# ADG3300-BREAKOUT.net
KiCad netlist of a schematic drawn in Altium Designer
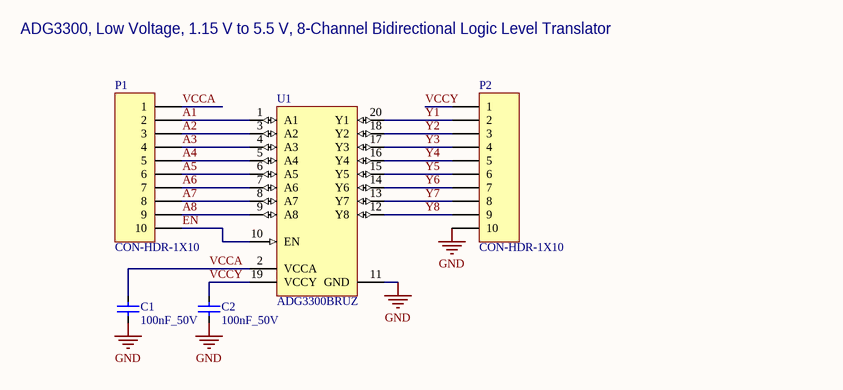
[diagram p0: ADG3300-BREAKOUT.SchDoc]

(export (version "E")
  (design (tool "Eeschema 10.0.6"))
  (components
    (comp (ref "C1")
      (value "100nF_50V")
      (footprint "CustomLib-Package:C0805")
      (description "50V 100nF X7R ±10% 0805 Multilayer Ceramic Capacitors MLCC - SMD/SMT ROHS")
      (fields (field (name "MANUFACTURER") "YAGEO") (field (name "Comment") "CC0805KRX7R9BB104"))
      (libsource (lib "CustomLib-Package") (part "CAPACITOR"))
    )
    (comp (ref "C2")
      (value "100nF_50V")
      (footprint "CustomLib-Package:C0805")
      (description "50V 100nF X7R ±10% 0805 Multilayer Ceramic Capacitors MLCC - SMD/SMT ROHS")
      (fields (field (name "MANUFACTURER") "YAGEO") (field (name "Comment") "CC0805KRX7R9BB104"))
      (libsource (lib "CustomLib-Package") (part "CAPACITOR"))
    )
    (comp (ref "P1")
      (value "CON-HDR-1X10")
      (footprint "CustomLib-Package:CON-HDR-1X10-2.54")
      (description "Pin Header, 10-Pin")
      (fields (field (name "PUBLISHER") "Altium Limited"))
      (libsource (lib "") (part "CON-HDR-1X10_1"))
    )
    (comp (ref "P2")
      (value "CON-HDR-1X10")
      (footprint "CustomLib-Package:CON-HDR-1X10-2.54")
      (description "Pin Header, 10-Pin")
      (fields (field (name "PUBLISHER") "Altium Limited"))
      (libsource (lib "CustomLib-Package") (part "CON-HDR-1X10"))
    )
    (comp (ref "U1")
      (value "ADG3300BRUZ")
      (footprint "CustomLib-Package:TSSOP-20")
      (fields (field (name "MANUFACTURER") "Analog Devices"))
      (libsource (lib "CustomLib-Package") (part "ADG3300"))
    )
  )
  (nets
    (net (code "1") (name "/A1") (class "Default")
      (node (ref "P1") (pin "2") (pinfunction "2_2") (pintype "passive"))
      (node (ref "U1") (pin "1") (pinfunction "A1_1") (pintype "bidirectional"))
    )
    (net (code "2") (name "/A2") (class "Default")
      (node (ref "P1") (pin "3") (pinfunction "3_3") (pintype "passive"))
      (node (ref "U1") (pin "3") (pinfunction "A2_3") (pintype "bidirectional"))
    )
    (net (code "3") (name "/A3") (class "Default")
      (node (ref "P1") (pin "4") (pinfunction "4_4") (pintype "passive"))
      (node (ref "U1") (pin "4") (pinfunction "A3_4") (pintype "bidirectional"))
    )
    (net (code "4") (name "/A4") (class "Default")
      (node (ref "P1") (pin "5") (pinfunction "5_5") (pintype "passive"))
      (node (ref "U1") (pin "5") (pinfunction "A4_5") (pintype "bidirectional"))
    )
    (net (code "5") (name "/A5") (class "Default")
      (node (ref "P1") (pin "6") (pinfunction "6_6") (pintype "passive"))
      (node (ref "U1") (pin "6") (pinfunction "A5_6") (pintype "bidirectional"))
    )
    (net (code "6") (name "/A6") (class "Default")
      (node (ref "P1") (pin "7") (pinfunction "7_7") (pintype "passive"))
      (node (ref "U1") (pin "7") (pinfunction "A6_7") (pintype "bidirectional"))
    )
    (net (code "7") (name "/A7") (class "Default")
      (node (ref "P1") (pin "8") (pinfunction "8_8") (pintype "passive"))
      (node (ref "U1") (pin "8") (pinfunction "A7_8") (pintype "bidirectional"))
    )
    (net (code "8") (name "/A8") (class "Default")
      (node (ref "P1") (pin "9") (pinfunction "9_9") (pintype "passive"))
      (node (ref "U1") (pin "9") (pinfunction "A8_9") (pintype "bidirectional"))
    )
    (net (code "9") (name "/EN") (class "Default")
      (node (ref "P1") (pin "10") (pinfunction "10_10") (pintype "passive"))
      (node (ref "U1") (pin "10") (pinfunction "EN_10") (pintype "input"))
    )
    (net (code "10") (name "/VCCA") (class "Default")
      (node (ref "C1") (pin "1") (pinfunction "1_1") (pintype "passive"))
      (node (ref "P1") (pin "1") (pinfunction "1_1") (pintype "passive"))
      (node (ref "U1") (pin "2") (pinfunction "VCCA_2") (pintype "power_in"))
    )
    (net (code "11") (name "/VCCY") (class "Default")
      (node (ref "C2") (pin "1") (pinfunction "1_1") (pintype "passive"))
      (node (ref "P2") (pin "1") (pinfunction "1_1") (pintype "passive"))
      (node (ref "U1") (pin "19") (pinfunction "VCCY_19") (pintype "power_in"))
    )
    (net (code "12") (name "/Y1") (class "Default")
      (node (ref "P2") (pin "2") (pinfunction "2_2") (pintype "passive"))
      (node (ref "U1") (pin "20") (pinfunction "Y1_20") (pintype "bidirectional"))
    )
    (net (code "13") (name "/Y2") (class "Default")
      (node (ref "P2") (pin "3") (pinfunction "3_3") (pintype "passive"))
      (node (ref "U1") (pin "18") (pinfunction "Y2_18") (pintype "bidirectional"))
    )
    (net (code "14") (name "/Y3") (class "Default")
      (node (ref "P2") (pin "4") (pinfunction "4_4") (pintype "passive"))
      (node (ref "U1") (pin "17") (pinfunction "Y3_17") (pintype "bidirectional"))
    )
    (net (code "15") (name "/Y4") (class "Default")
      (node (ref "P2") (pin "5") (pinfunction "5_5") (pintype "passive"))
      (node (ref "U1") (pin "16") (pinfunction "Y4_16") (pintype "bidirectional"))
    )
    (net (code "16") (name "/Y5") (class "Default")
      (node (ref "P2") (pin "6") (pinfunction "6_6") (pintype "passive"))
      (node (ref "U1") (pin "15") (pinfunction "Y5_15") (pintype "bidirectional"))
    )
    (net (code "17") (name "/Y6") (class "Default")
      (node (ref "P2") (pin "7") (pinfunction "7_7") (pintype "passive"))
      (node (ref "U1") (pin "14") (pinfunction "Y6_14") (pintype "bidirectional"))
    )
    (net (code "18") (name "/Y7") (class "Default")
      (node (ref "P2") (pin "8") (pinfunction "8_8") (pintype "passive"))
      (node (ref "U1") (pin "13") (pinfunction "Y7_13") (pintype "bidirectional"))
    )
    (net (code "19") (name "/Y8") (class "Default")
      (node (ref "P2") (pin "9") (pinfunction "9_9") (pintype "passive"))
      (node (ref "U1") (pin "12") (pinfunction "Y8_12") (pintype "bidirectional"))
    )
    (net (code "20") (name "GND") (class "Default")
      (node (ref "C1") (pin "2") (pinfunction "2_2") (pintype "passive"))
      (node (ref "C2") (pin "2") (pinfunction "2_2") (pintype "passive"))
      (node (ref "P2") (pin "10") (pinfunction "10_10") (pintype "passive"))
      (node (ref "U1") (pin "11") (pinfunction "GND_11") (pintype "power_in"))
    )
  )
)
